# FEM.net
KiCad netlist of a schematic drawn in Altium Designer
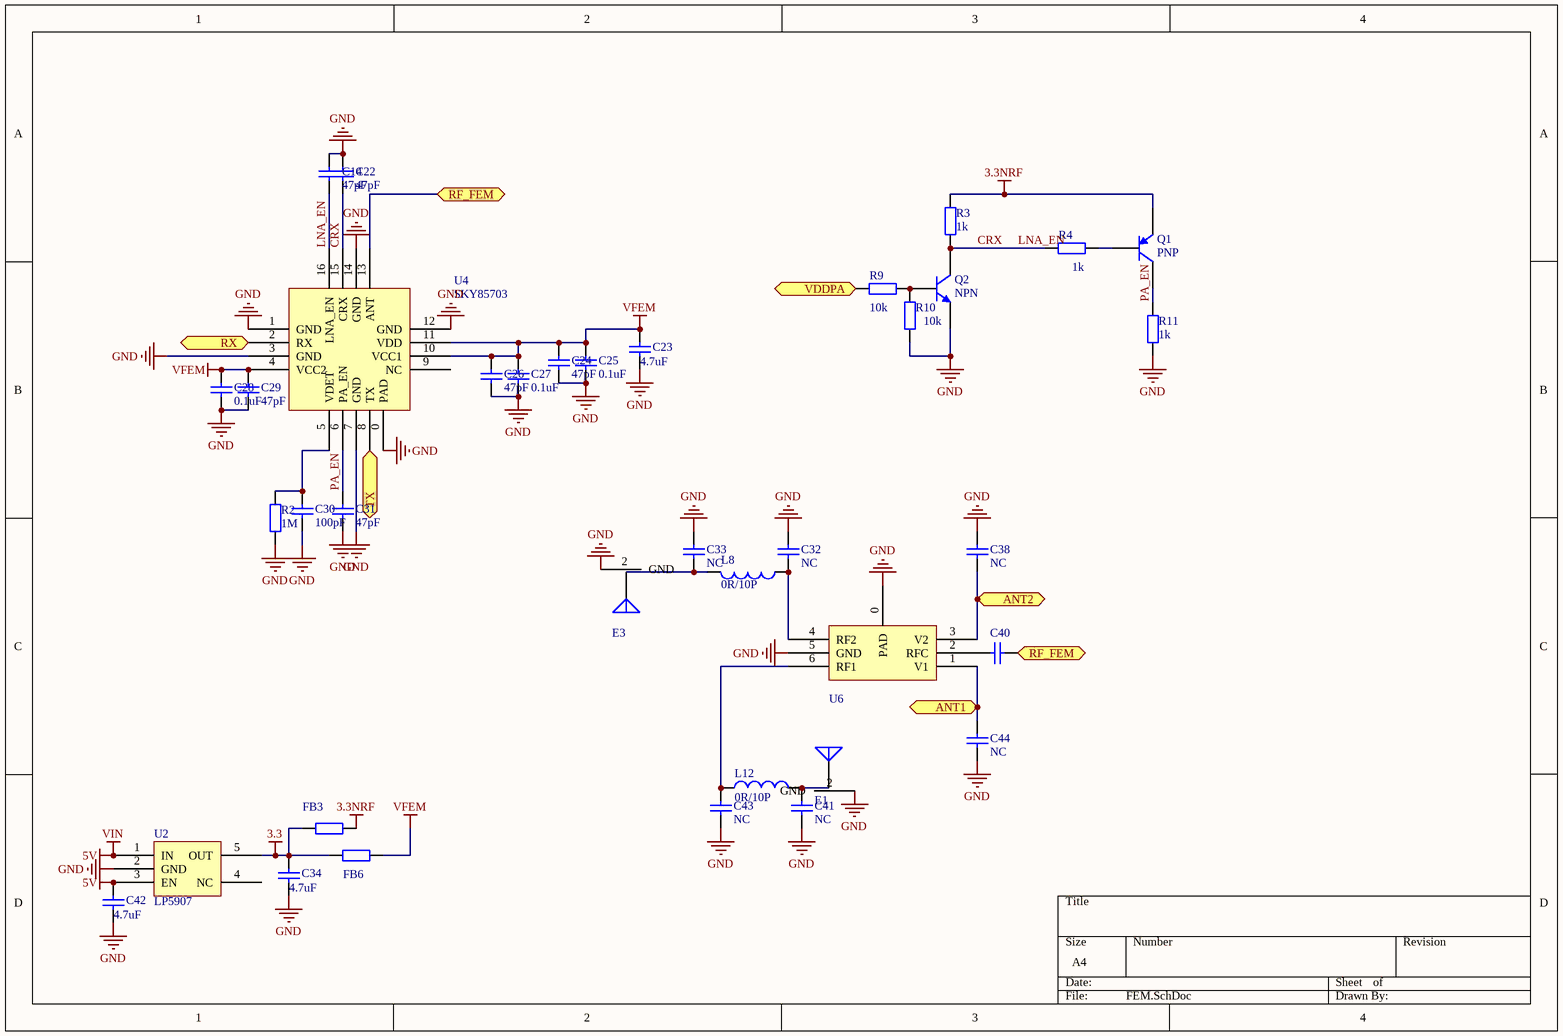
[diagram p0: FEM.SchDoc]

(export (version "E")
  (design (tool "Eeschema 10.0.6"))
  (components
    (comp (ref "C14")
      (value "47pF")
      (footprint "0402")
      (description "Capacitor")
      (fields (field (name "PUBLISHER") "Altium Limited"))
      (libsource (lib "RTC6705") (part "Cap"))
    )
    (comp (ref "C22")
      (value "47pF")
      (footprint "0402")
      (description "Capacitor")
      (fields (field (name "PUBLISHER") "Altium Limited"))
      (libsource (lib "RTC6705") (part "Cap"))
    )
    (comp (ref "C23")
      (value "4.7uF")
      (footprint "0805")
      (description "Capacitor")
      (fields (field (name "PUBLISHER") "Altium Limited"))
      (libsource (lib "RTC6705") (part "Cap"))
    )
    (comp (ref "C24")
      (value "47pF")
      (footprint "0402")
      (description "Capacitor")
      (fields (field (name "PUBLISHER") "Altium Limited"))
      (libsource (lib "RTC6705") (part "Cap"))
    )
    (comp (ref "C25")
      (value "0.1uF")
      (footprint "0402")
      (description "Capacitor")
      (fields (field (name "PUBLISHER") "Altium Limited"))
      (libsource (lib "RTC6705") (part "Cap"))
    )
    (comp (ref "C26")
      (value "47pF")
      (footprint "0402")
      (description "Capacitor")
      (fields (field (name "PUBLISHER") "Altium Limited"))
      (libsource (lib "RTC6705") (part "Cap"))
    )
    (comp (ref "C27")
      (value "0.1uF")
      (footprint "0402")
      (description "Capacitor")
      (fields (field (name "PUBLISHER") "Altium Limited"))
      (libsource (lib "RTC6705") (part "Cap"))
    )
    (comp (ref "C28")
      (value "0.1uF")
      (footprint "0402")
      (description "Capacitor")
      (fields (field (name "PUBLISHER") "Altium Limited"))
      (libsource (lib "RTC6705") (part "Cap"))
    )
    (comp (ref "C29")
      (value "47pF")
      (footprint "0402")
      (description "Capacitor")
      (fields (field (name "PUBLISHER") "Altium Limited"))
      (libsource (lib "RTC6705") (part "Cap"))
    )
    (comp (ref "C30")
      (value "100pF")
      (footprint "0402")
      (description "Capacitor")
      (fields (field (name "PUBLISHER") "Altium Limited"))
      (libsource (lib "RTC6705") (part "Cap"))
    )
    (comp (ref "C31")
      (value "47pF")
      (footprint "0402")
      (description "Capacitor")
      (fields (field (name "PUBLISHER") "Altium Limited"))
      (libsource (lib "RTC6705") (part "Cap"))
    )
    (comp (ref "C32")
      (value "NC")
      (footprint "0402")
      (description "Capacitor")
      (fields (field (name "PUBLISHER") "Altium Limited"))
      (libsource (lib "RTC6705") (part "Cap"))
    )
    (comp (ref "C33")
      (value "NC")
      (footprint "0402")
      (description "Capacitor")
      (fields (field (name "PUBLISHER") "Altium Limited"))
      (libsource (lib "RTC6705") (part "Cap"))
    )
    (comp (ref "C34")
      (value "4.7uF")
      (footprint "0603")
      (description "Capacitor")
      (fields (field (name "PUBLISHER") "Altium Limited"))
      (libsource (lib "RTC6705") (part "Cap"))
    )
    (comp (ref "C38")
      (value "NC")
      (footprint "0402")
      (description "Capacitor")
      (fields (field (name "Comment") "Cap") (field (name "PUBLISHER") "Altium Limited"))
      (libsource (lib "RTC6705") (part "Cap"))
    )
    (comp (ref "C40")
      (value "10p")
      (footprint "0402")
      (description "Capacitor")
      (fields (field (name "PUBLISHER") "Altium Limited"))
      (libsource (lib "RTC6705") (part "Cap"))
    )
    (comp (ref "C41")
      (value "NC")
      (footprint "0402")
      (description "Capacitor")
      (fields (field (name "Comment") "Cap") (field (name "PUBLISHER") "Altium Limited"))
      (libsource (lib "RTC6705") (part "Cap"))
    )
    (comp (ref "C42")
      (value "4.7uF")
      (footprint "0603")
      (description "Capacitor")
      (fields (field (name "PUBLISHER") "Altium Limited"))
      (libsource (lib "RTC6705") (part "Cap"))
    )
    (comp (ref "C43")
      (value "NC")
      (footprint "0402")
      (description "Capacitor")
      (fields (field (name "Comment") "Cap") (field (name "PUBLISHER") "Altium Limited"))
      (libsource (lib "RTC6705") (part "Cap"))
    )
    (comp (ref "C44")
      (value "NC")
      (footprint "0402")
      (description "Capacitor")
      (fields (field (name "Comment") "Cap") (field (name "PUBLISHER") "Altium Limited"))
      (libsource (lib "RTC6705") (part "Cap"))
    )
    (comp (ref "E1")
      (value "Antenna")
      (footprint "IPEX")
      (description "Generic Antenna")
      (fields (field (name "PUBLISHER") "Altium Limited"))
      (libsource (lib "Miscellaneous Devices") (part "Antenna"))
    )
    (comp (ref "E3")
      (value "Antenna")
      (footprint "IPEX")
      (description "Generic Antenna")
      (fields (field (name "PUBLISHER") "Altium Limited"))
      (libsource (lib "Miscellaneous Devices") (part "Antenna"))
    )
    (comp (ref "FB3")
      (value "Res2")
      (footprint "0402")
      (description "Resistor")
      (fields (field (name "PUBLISHER") "Altium Limited"))
      (libsource (lib "") (part "Res2_1"))
    )
    (comp (ref "FB6")
      (value "Res2")
      (footprint "0402")
      (description "Resistor")
      (fields (field (name "PUBLISHER") "Altium Limited"))
      (libsource (lib "") (part "Res2_1"))
    )
    (comp (ref "L8")
      (value "0R/10P")
      (footprint "0402")
      (description "Inductor")
      (fields (field (name "PUBLISHER") "Altium Limited"))
      (libsource (lib "Miscellaneous Devices") (part "Inductor"))
    )
    (comp (ref "L12")
      (value "0R/10P")
      (footprint "0402")
      (description "Inductor")
      (fields (field (name "PUBLISHER") "Altium Limited"))
      (libsource (lib "Miscellaneous Devices") (part "Inductor"))
    )
    (comp (ref "Q1")
      (value "PNP")
      (footprint "LC-SOT-323(SC-70)")
      (description "PNP Bipolar Transistor")
      (fields (field (name "PUBLISHER") "Altium Limited"))
      (libsource (lib "BK5811FEM") (part "PNP"))
    )
    (comp (ref "Q2")
      (value "NPN")
      (footprint "LC-SOT-323(SC-70)")
      (description "NPN Bipolar Transistor")
      (fields (field (name "PUBLISHER") "Altium Limited"))
      (libsource (lib "BK5811FEM") (part "NPN"))
    )
    (comp (ref "R2")
      (value "1M")
      (footprint "0402")
      (description "Resistor")
      (fields (field (name "Comment") "Res2") (field (name "PUBLISHER") "Altium Limited"))
      (libsource (lib "") (part "Res2_2"))
    )
    (comp (ref "R3")
      (value "1k")
      (footprint "0402")
      (description "Resistor")
      (fields (field (name "Comment") "Res2") (field (name "PUBLISHER") "Altium Limited"))
      (libsource (lib "") (part "Res2_2"))
    )
    (comp (ref "R4")
      (value "1k")
      (footprint "0402")
      (description "Resistor")
      (fields (field (name "Comment") "Res2") (field (name "PUBLISHER") "Altium Limited"))
      (libsource (lib "") (part "Res2_1"))
    )
    (comp (ref "R9")
      (value "10k")
      (footprint "0402")
      (description "Resistor")
      (fields (field (name "PUBLISHER") "Altium Limited"))
      (libsource (lib "") (part "Res2_1"))
    )
    (comp (ref "R10")
      (value "10k")
      (footprint "0402")
      (description "Resistor")
      (fields (field (name "PUBLISHER") "Altium Limited"))
      (libsource (lib "RTC6705") (part "Res2"))
    )
    (comp (ref "R11")
      (value "1k")
      (footprint "0402")
      (description "Resistor")
      (fields (field (name "Comment") "Res2") (field (name "PUBLISHER") "Altium Limited"))
      (libsource (lib "RTC6705") (part "Res2"))
    )
    (comp (ref "U2") (value "LP5907") (footprint "SOT23-5") (libsource (lib "RTC6705") (part "LP5907")))
    (comp (ref "U4") (value "SKY85703") (footprint "QFN16-3x3") (libsource (lib "BK5811") (part "SKY85703")))
    (comp (ref "U6")
      (value "SKY13370-374LF")
      (footprint "SKY65404-31")
      (libsource (lib "BK5811") (part "SKY13370-374LF"))
    )
  )
  (nets
    (net (code "1") (name "/ANT1") (class "Default")
      (node (ref "C44") (pin "2") (pinfunction "2_2") (pintype "passive"))
      (node (ref "U6") (pin "1") (pinfunction "V1_1") (pintype "passive"))
    )
    (net (code "2") (name "/ANT2") (class "Default")
      (node (ref "C38") (pin "2") (pinfunction "2_2") (pintype "passive"))
      (node (ref "U6") (pin "3") (pinfunction "V2_3") (pintype "passive"))
    )
    (net (code "3") (name "/CRX") (class "Default")
      (node (ref "C14") (pin "1") (pinfunction "1_1") (pintype "passive"))
      (node (ref "C22") (pin "2") (pinfunction "2_2") (pintype "passive"))
      (node (ref "Q2") (pin "3") (pinfunction "C_3") (pintype "passive"))
      (node (ref "R3") (pin "2") (pinfunction "2_2") (pintype "passive"))
      (node (ref "R4") (pin "1") (pinfunction "1_1") (pintype "passive"))
      (node (ref "U4") (pin "15") (pinfunction "CRX_15") (pintype "passive"))
      (node (ref "U4") (pin "16") (pinfunction "LNA_EN_16") (pintype "passive"))
    )
    (net (code "4") (name "/PA_EN") (class "Default")
      (node (ref "C31") (pin "2") (pinfunction "2_2") (pintype "passive"))
      (node (ref "Q1") (pin "3") (pinfunction "C_3") (pintype "passive"))
      (node (ref "R11") (pin "2") (pinfunction "2_2") (pintype "passive"))
      (node (ref "U4") (pin "6") (pinfunction "PA_EN_6") (pintype "passive"))
    )
    (net (code "5") (name "/RF_FEM") (class "Default")
      (node (ref "C40") (pin "2") (pinfunction "2_2") (pintype "passive"))
      (node (ref "U4") (pin "13") (pinfunction "ANT_13") (pintype "passive"))
    )
    (net (code "6") (name "/RX") (class "Default")
      (node (ref "U4") (pin "2") (pinfunction "RX_2") (pintype "passive"))
    )
    (net (code "7") (name "/TX") (class "Default")
      (node (ref "U4") (pin "8") (pinfunction "TX_8") (pintype "passive"))
    )
    (net (code "8") (name "/VDDPA") (class "Default")
      (node (ref "R9") (pin "1") (pinfunction "1_1") (pintype "passive"))
    )
    (net (code "9") (name "3.3") (class "Default")
      (node (ref "C34") (pin "2") (pinfunction "2_2") (pintype "passive"))
      (node (ref "FB3") (pin "1") (pinfunction "1_1") (pintype "passive"))
      (node (ref "FB6") (pin "1") (pinfunction "1_1") (pintype "passive"))
      (node (ref "U2") (pin "5") (pinfunction "OUT_5") (pintype "passive"))
    )
    (net (code "10") (name "3.3NRF") (class "Default")
      (node (ref "FB3") (pin "2") (pinfunction "2_2") (pintype "passive"))
      (node (ref "Q1") (pin "2") (pinfunction "E_2") (pintype "passive"))
      (node (ref "R3") (pin "1") (pinfunction "1_1") (pintype "passive"))
    )
    (net (code "11") (name "5V") (class "Default")
      (node (ref "C42") (pin "2") (pinfunction "2_2") (pintype "passive"))
      (node (ref "U2") (pin "1") (pinfunction "IN_1") (pintype "passive"))
      (node (ref "U2") (pin "3") (pinfunction "EN_3") (pintype "passive"))
    )
    (net (code "12") (name "GND") (class "Default")
      (node (ref "C14") (pin "2") (pinfunction "2_2") (pintype "passive"))
      (node (ref "C22") (pin "1") (pinfunction "1_1") (pintype "passive"))
      (node (ref "C23") (pin "1") (pinfunction "1_1") (pintype "passive"))
      (node (ref "C24") (pin "1") (pinfunction "1_1") (pintype "passive"))
      (node (ref "C25") (pin "1") (pinfunction "1_1") (pintype "passive"))
      (node (ref "C26") (pin "1") (pinfunction "1_1") (pintype "passive"))
      (node (ref "C27") (pin "1") (pinfunction "1_1") (pintype "passive"))
      (node (ref "C28") (pin "1") (pinfunction "1_1") (pintype "passive"))
      (node (ref "C29") (pin "1") (pinfunction "1_1") (pintype "passive"))
      (node (ref "C30") (pin "1") (pinfunction "1_1") (pintype "passive"))
      (node (ref "C31") (pin "1") (pinfunction "1_1") (pintype "passive"))
      (node (ref "C32") (pin "1") (pinfunction "1_1") (pintype "passive"))
      (node (ref "C33") (pin "1") (pinfunction "1_1") (pintype "passive"))
      (node (ref "C34") (pin "1") (pinfunction "1_1") (pintype "passive"))
      (node (ref "C38") (pin "1") (pinfunction "1_1") (pintype "passive"))
      (node (ref "C41") (pin "2") (pinfunction "2_2") (pintype "passive"))
      (node (ref "C42") (pin "1") (pinfunction "1_1") (pintype "passive"))
      (node (ref "C43") (pin "2") (pinfunction "2_2") (pintype "passive"))
      (node (ref "C44") (pin "1") (pinfunction "1_1") (pintype "passive"))
      (node (ref "E1") (pin "2") (pinfunction "GND_2") (pintype "passive"))
      (node (ref "E3") (pin "2") (pinfunction "GND_2") (pintype "passive"))
      (node (ref "Q2") (pin "2") (pinfunction "E_2") (pintype "passive"))
      (node (ref "R10") (pin "1") (pinfunction "1_1") (pintype "passive"))
      (node (ref "R11") (pin "1") (pinfunction "1_1") (pintype "passive"))
      (node (ref "R2") (pin "2") (pinfunction "2_2") (pintype "passive"))
      (node (ref "U2") (pin "2") (pinfunction "GND_2") (pintype "passive"))
      (node (ref "U4") (pin "0") (pinfunction "PAD_0") (pintype "passive"))
      (node (ref "U4") (pin "1") (pinfunction "GND_1") (pintype "passive"))
      (node (ref "U4") (pin "12") (pinfunction "GND_12") (pintype "passive"))
      (node (ref "U4") (pin "14") (pinfunction "GND_14") (pintype "passive"))
      (node (ref "U4") (pin "3") (pinfunction "GND_3") (pintype "passive"))
      (node (ref "U4") (pin "7") (pinfunction "GND_7") (pintype "passive"))
      (node (ref "U6") (pin "0") (pinfunction "PAD_0") (pintype "passive"))
      (node (ref "U6") (pin "5") (pinfunction "GND_5") (pintype "passive"))
    )
    (net (code "13") (name "Net-(E1-ANT)") (class "Default")
      (node (ref "C41") (pin "1") (pinfunction "1_1") (pintype "passive"))
      (node (ref "E1") (pin "1") (pinfunction "ANT_1") (pintype "passive"))
      (node (ref "L12") (pin "2") (pinfunction "2_2") (pintype "passive"))
    )
    (net (code "14") (name "Net-(E3-ANT)") (class "Default")
      (node (ref "C33") (pin "2") (pinfunction "2_2") (pintype "passive"))
      (node (ref "E3") (pin "1") (pinfunction "ANT_1") (pintype "passive"))
      (node (ref "L8") (pin "2") (pinfunction "2_2") (pintype "passive"))
    )
    (net (code "15") (name "Net-(Q1-B)") (class "Default")
      (node (ref "Q1") (pin "1") (pinfunction "B_1") (pintype "passive"))
      (node (ref "R4") (pin "2") (pinfunction "2_2") (pintype "passive"))
    )
    (net (code "16") (name "Net-(Q2-B)") (class "Default")
      (node (ref "Q2") (pin "1") (pinfunction "B_1") (pintype "passive"))
      (node (ref "R10") (pin "2") (pinfunction "2_2") (pintype "passive"))
      (node (ref "R9") (pin "2") (pinfunction "2_2") (pintype "passive"))
    )
    (net (code "17") (name "Net-(U4-VDET)") (class "Default")
      (node (ref "C30") (pin "2") (pinfunction "2_2") (pintype "passive"))
      (node (ref "R2") (pin "1") (pinfunction "1_1") (pintype "passive"))
      (node (ref "U4") (pin "5") (pinfunction "VDET_5") (pintype "passive"))
    )
    (net (code "18") (name "Net-(U6-RF1)") (class "Default")
      (node (ref "C43") (pin "1") (pinfunction "1_1") (pintype "passive"))
      (node (ref "L12") (pin "1") (pinfunction "1_1") (pintype "passive"))
      (node (ref "U6") (pin "6") (pinfunction "RF1_6") (pintype "passive"))
    )
    (net (code "19") (name "Net-(U6-RF2)") (class "Default")
      (node (ref "C32") (pin "2") (pinfunction "2_2") (pintype "passive"))
      (node (ref "L8") (pin "1") (pinfunction "1_1") (pintype "passive"))
      (node (ref "U6") (pin "4") (pinfunction "RF2_4") (pintype "passive"))
    )
    (net (code "20") (name "Net-(U6-RFC)") (class "Default")
      (node (ref "C40") (pin "1") (pinfunction "1_1") (pintype "passive"))
      (node (ref "U6") (pin "2") (pinfunction "RFC_2") (pintype "passive"))
    )
    (net (code "21") (name "VFEM") (class "Default")
      (node (ref "C23") (pin "2") (pinfunction "2_2") (pintype "passive"))
      (node (ref "C24") (pin "2") (pinfunction "2_2") (pintype "passive"))
      (node (ref "C25") (pin "2") (pinfunction "2_2") (pintype "passive"))
      (node (ref "C26") (pin "2") (pinfunction "2_2") (pintype "passive"))
      (node (ref "C27") (pin "2") (pinfunction "2_2") (pintype "passive"))
      (node (ref "C28") (pin "2") (pinfunction "2_2") (pintype "passive"))
      (node (ref "C29") (pin "2") (pinfunction "2_2") (pintype "passive"))
      (node (ref "FB6") (pin "2") (pinfunction "2_2") (pintype "passive"))
      (node (ref "U4") (pin "10") (pinfunction "VCC1_10") (pintype "passive"))
      (node (ref "U4") (pin "11") (pinfunction "VDD_11") (pintype "passive"))
      (node (ref "U4") (pin "4") (pinfunction "VCC2_4") (pintype "passive"))
    )
    (net (code "22") (name "unconnected-(U2-NC-Pad4)") (class "Default")
      (node (ref "U2") (pin "4") (pinfunction "NC_4") (pintype "passive"))
    )
    (net (code "23") (name "unconnected-(U4-NC-Pad9)") (class "Default")
      (node (ref "U4") (pin "9") (pinfunction "NC_9") (pintype "passive"))
    )
  )
)
